# LED-OtherCat.net
KiCad netlist of a schematic drawn in EAGLE
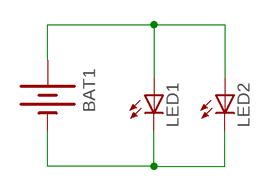
[diagram p0: schematic, sheet 1]

(export (version "E")
  (design (tool "Eeschema 10.0.6"))
  (components
    (comp (ref "BAT1")
      (value "BATTERY20PTH")
      (footprint "eagle-import:BATTCOM_20MM_PTH")
      (libsource (lib "eagle-import") (part "BATTERY20PTH"))
    )
    (comp (ref "LED1")
      (value "LEDP-LCC-2-BACK")
      (footprint "eagle-import:P-LCC-2-TOPLED-RG")
      (libsource (lib "eagle-import") (part "LEDP-LCC-2-BACK"))
    )
    (comp (ref "LED2")
      (value "LEDP-LCC-2-BACK")
      (footprint "eagle-import:P-LCC-2-TOPLED-RG")
      (libsource (lib "eagle-import") (part "LEDP-LCC-2-BACK"))
    )
  )
  (nets
    (net (code "1") (name "Net-(BAT1-+)") (class "Default")
      (node (ref "BAT1") (pin "1") (pinfunction "+_1") (pintype "power_in"))
      (node (ref "LED1") (pin "A") (pinfunction "A_A") (pintype "passive"))
      (node (ref "LED2") (pin "A") (pinfunction "A_A") (pintype "passive"))
    )
    (net (code "2") (name "Net-(BAT1--)") (class "Default")
      (node (ref "BAT1") (pin "2") (pinfunction "-_2") (pintype "power_in"))
      (node (ref "LED1") (pin "C") (pinfunction "C_C") (pintype "passive"))
      (node (ref "LED2") (pin "C") (pinfunction "C_C") (pintype "passive"))
    )
  )
)
